# power_control.net
KiCad netlist of a schematic drawn in EAGLE
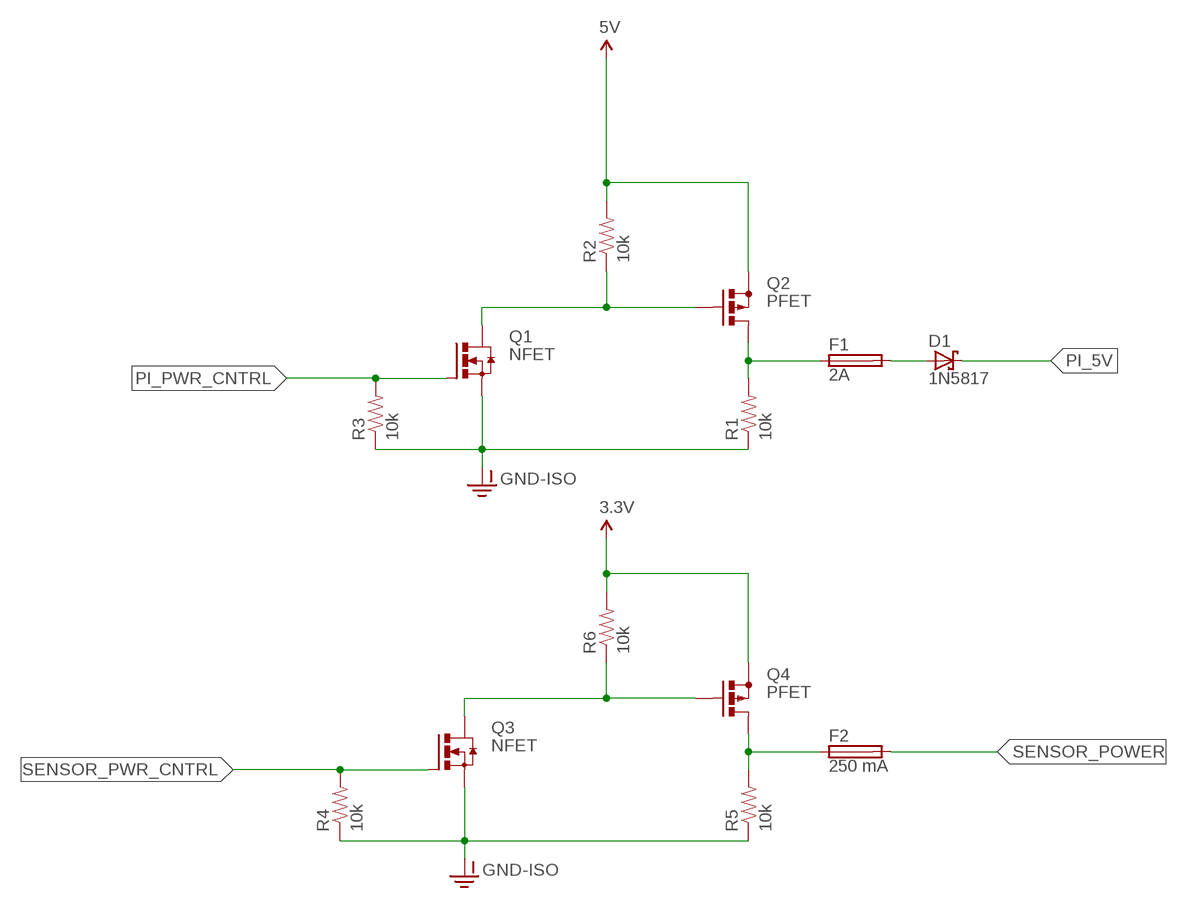
[diagram p0: schematic, sheet 1]

(export (version "E")
  (design (tool "Eeschema 10.0.6"))
  (components
    (comp (ref "D1")
      (value "1N5817")
      (footprint "eagle-import:CB429-15")
      (libsource (lib "eagle-import") (part "SCHOTTKY-DIODECB429-15"))
    )
    (comp (ref "F1")
      (value "2A")
      (footprint "eagle-import:PICOFUSE")
      (libsource (lib "eagle-import") (part "FUSEPICOFUSE"))
    )
    (comp (ref "F2")
      (value "250 mA")
      (footprint "eagle-import:PICOFUSE")
      (libsource (lib "eagle-import") (part "FUSEPICOFUSE"))
    )
    (comp (ref "Q1")
      (value "NFET")
      (footprint "eagle-import:TO220AH")
      (libsource (lib "eagle-import") (part "IRF3704"))
    )
    (comp (ref "Q2")
      (value "PFET")
      (footprint "eagle-import:TO92-OVAL")
      (libsource (lib "eagle-import") (part "PFETBS250"))
    )
    (comp (ref "Q3")
      (value "NFET")
      (footprint "eagle-import:TO220AH")
      (libsource (lib "eagle-import") (part "IRF3704"))
    )
    (comp (ref "Q4")
      (value "PFET")
      (footprint "eagle-import:TO92-OVAL")
      (libsource (lib "eagle-import") (part "PFETBS250"))
    )
    (comp (ref "R1")
      (value "10k")
      (footprint "eagle-import:1206")
      (libsource (lib "eagle-import") (part "RESISTOR1206"))
    )
    (comp (ref "R2")
      (value "10k")
      (footprint "eagle-import:1206")
      (libsource (lib "eagle-import") (part "RESISTOR1206"))
    )
    (comp (ref "R3")
      (value "10k")
      (footprint "eagle-import:1206")
      (libsource (lib "eagle-import") (part "RESISTOR1206"))
    )
    (comp (ref "R4")
      (value "10k")
      (footprint "eagle-import:1206")
      (libsource (lib "eagle-import") (part "RESISTOR1206"))
    )
    (comp (ref "R5")
      (value "10k")
      (footprint "eagle-import:1206")
      (libsource (lib "eagle-import") (part "RESISTOR1206"))
    )
    (comp (ref "R6")
      (value "10k")
      (footprint "eagle-import:1206")
      (libsource (lib "eagle-import") (part "RESISTOR1206"))
    )
  )
  (nets
    (net (code "1") (name "3.3V") (class "Default")
      (node (ref "Q4") (pin "3") (pinfunction "S_3") (pintype "passive"))
      (node (ref "R6") (pin "2") (pinfunction "2_2") (pintype "passive"))
    )
    (net (code "2") (name "5V") (class "Default")
      (node (ref "Q2") (pin "3") (pinfunction "S_3") (pintype "passive"))
      (node (ref "R2") (pin "2") (pinfunction "2_2") (pintype "passive"))
    )
    (net (code "3") (name "GND-ISO") (class "Default")
      (node (ref "Q1") (pin "E") (pinfunction "S_E") (pintype "passive"))
      (node (ref "Q3") (pin "E") (pinfunction "S_E") (pintype "passive"))
      (node (ref "R1") (pin "1") (pinfunction "1_1") (pintype "passive"))
      (node (ref "R3") (pin "1") (pinfunction "1_1") (pintype "passive"))
      (node (ref "R4") (pin "1") (pinfunction "1_1") (pintype "passive"))
      (node (ref "R5") (pin "1") (pinfunction "1_1") (pintype "passive"))
    )
    (net (code "4") (name "Net-(D1-PadA)") (class "Default")
      (node (ref "D1") (pin "A") (pinfunction "A_A") (pintype "passive"))
      (node (ref "F1") (pin "2") (pinfunction "2_2") (pintype "passive"))
    )
    (net (code "5") (name "Net-(Q1-D)") (class "Default")
      (node (ref "Q1") (pin "C") (pinfunction "D_C") (pintype "passive"))
      (node (ref "Q2") (pin "2") (pinfunction "G_2") (pintype "passive"))
      (node (ref "R2") (pin "1") (pinfunction "1_1") (pintype "passive"))
    )
    (net (code "6") (name "Net-(Q2-D)") (class "Default")
      (node (ref "F1") (pin "1") (pinfunction "1_1") (pintype "passive"))
      (node (ref "Q2") (pin "1") (pinfunction "D_1") (pintype "passive"))
      (node (ref "R1") (pin "2") (pinfunction "2_2") (pintype "passive"))
    )
    (net (code "7") (name "Net-(Q3-D)") (class "Default")
      (node (ref "Q3") (pin "C") (pinfunction "D_C") (pintype "passive"))
      (node (ref "Q4") (pin "2") (pinfunction "G_2") (pintype "passive"))
      (node (ref "R6") (pin "1") (pinfunction "1_1") (pintype "passive"))
    )
    (net (code "8") (name "Net-(Q4-D)") (class "Default")
      (node (ref "F2") (pin "1") (pinfunction "1_1") (pintype "passive"))
      (node (ref "Q4") (pin "1") (pinfunction "D_1") (pintype "passive"))
      (node (ref "R5") (pin "2") (pinfunction "2_2") (pintype "passive"))
    )
    (net (code "9") (name "PI_5V") (class "Default")
      (node (ref "D1") (pin "C") (pinfunction "C_C") (pintype "passive"))
    )
    (net (code "10") (name "PI_PWR_CNTRL") (class "Default")
      (node (ref "Q1") (pin "B") (pinfunction "G_B") (pintype "passive"))
      (node (ref "R3") (pin "2") (pinfunction "2_2") (pintype "passive"))
    )
    (net (code "11") (name "SENSOR_POWER") (class "Default")
      (node (ref "F2") (pin "2") (pinfunction "2_2") (pintype "passive"))
    )
    (net (code "12") (name "SENSOR_PWR_CNTRL") (class "Default")
      (node (ref "Q3") (pin "B") (pinfunction "G_B") (pintype "passive"))
      (node (ref "R4") (pin "2") (pinfunction "2_2") (pintype "passive"))
    )
  )
)
